# TouchGlove.net
KiCad netlist of a schematic drawn in EAGLE
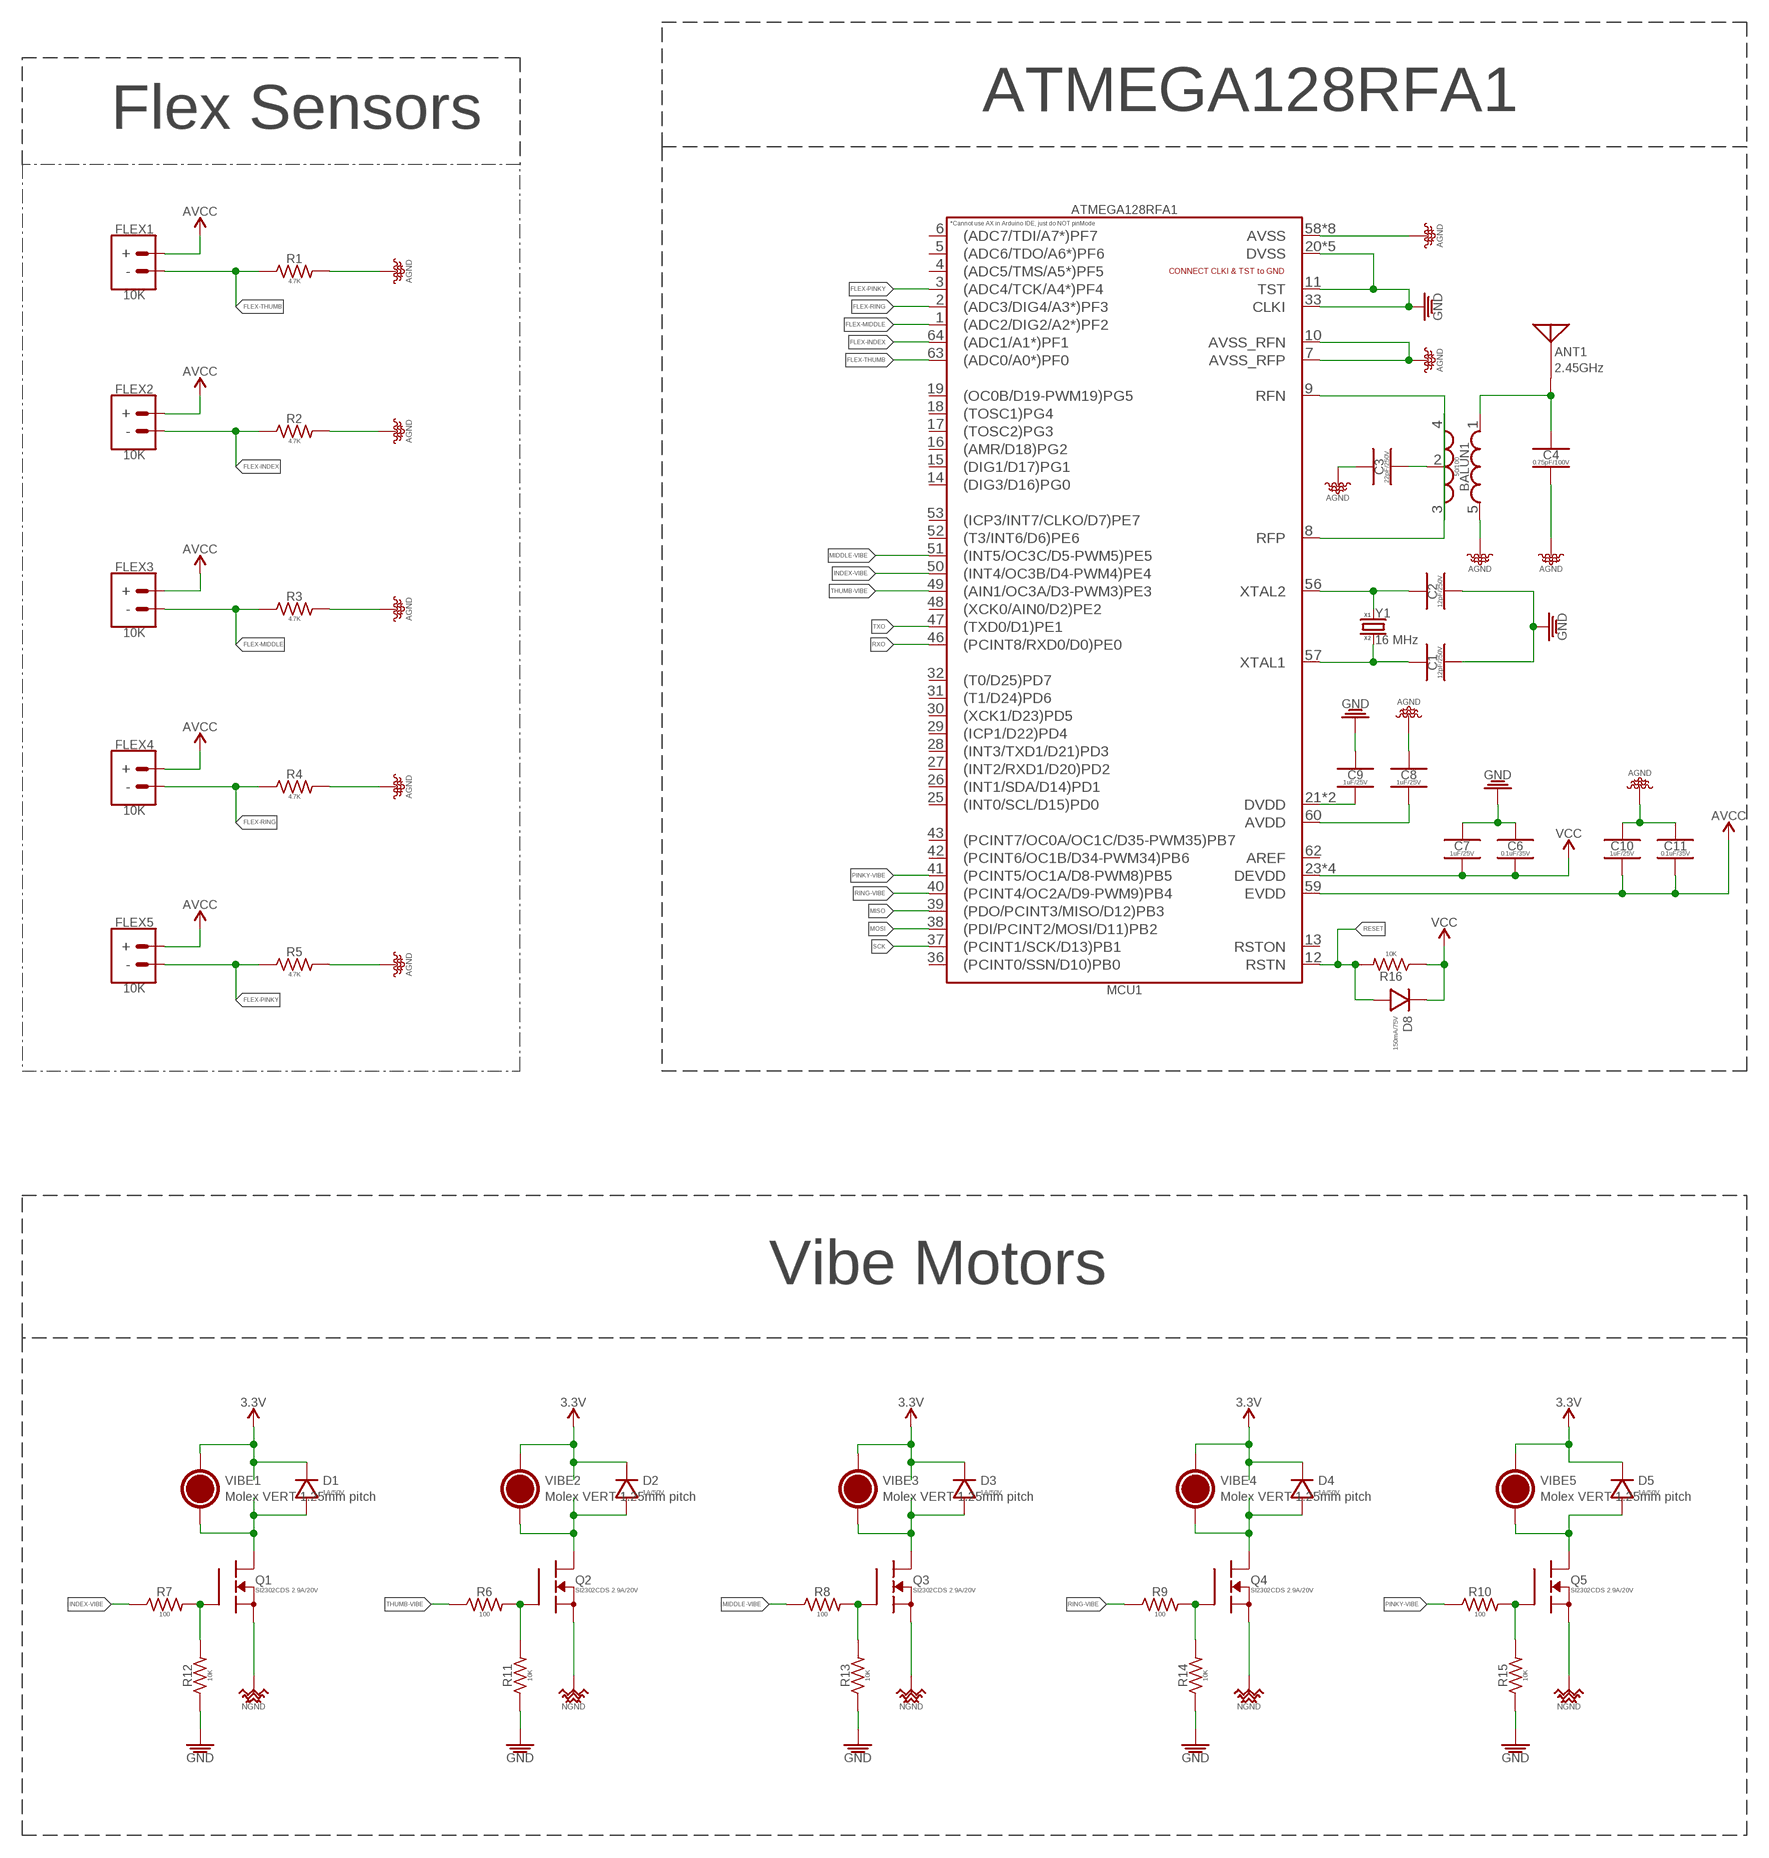
[diagram p0: schematic, sheet 1, part 1 of 2]
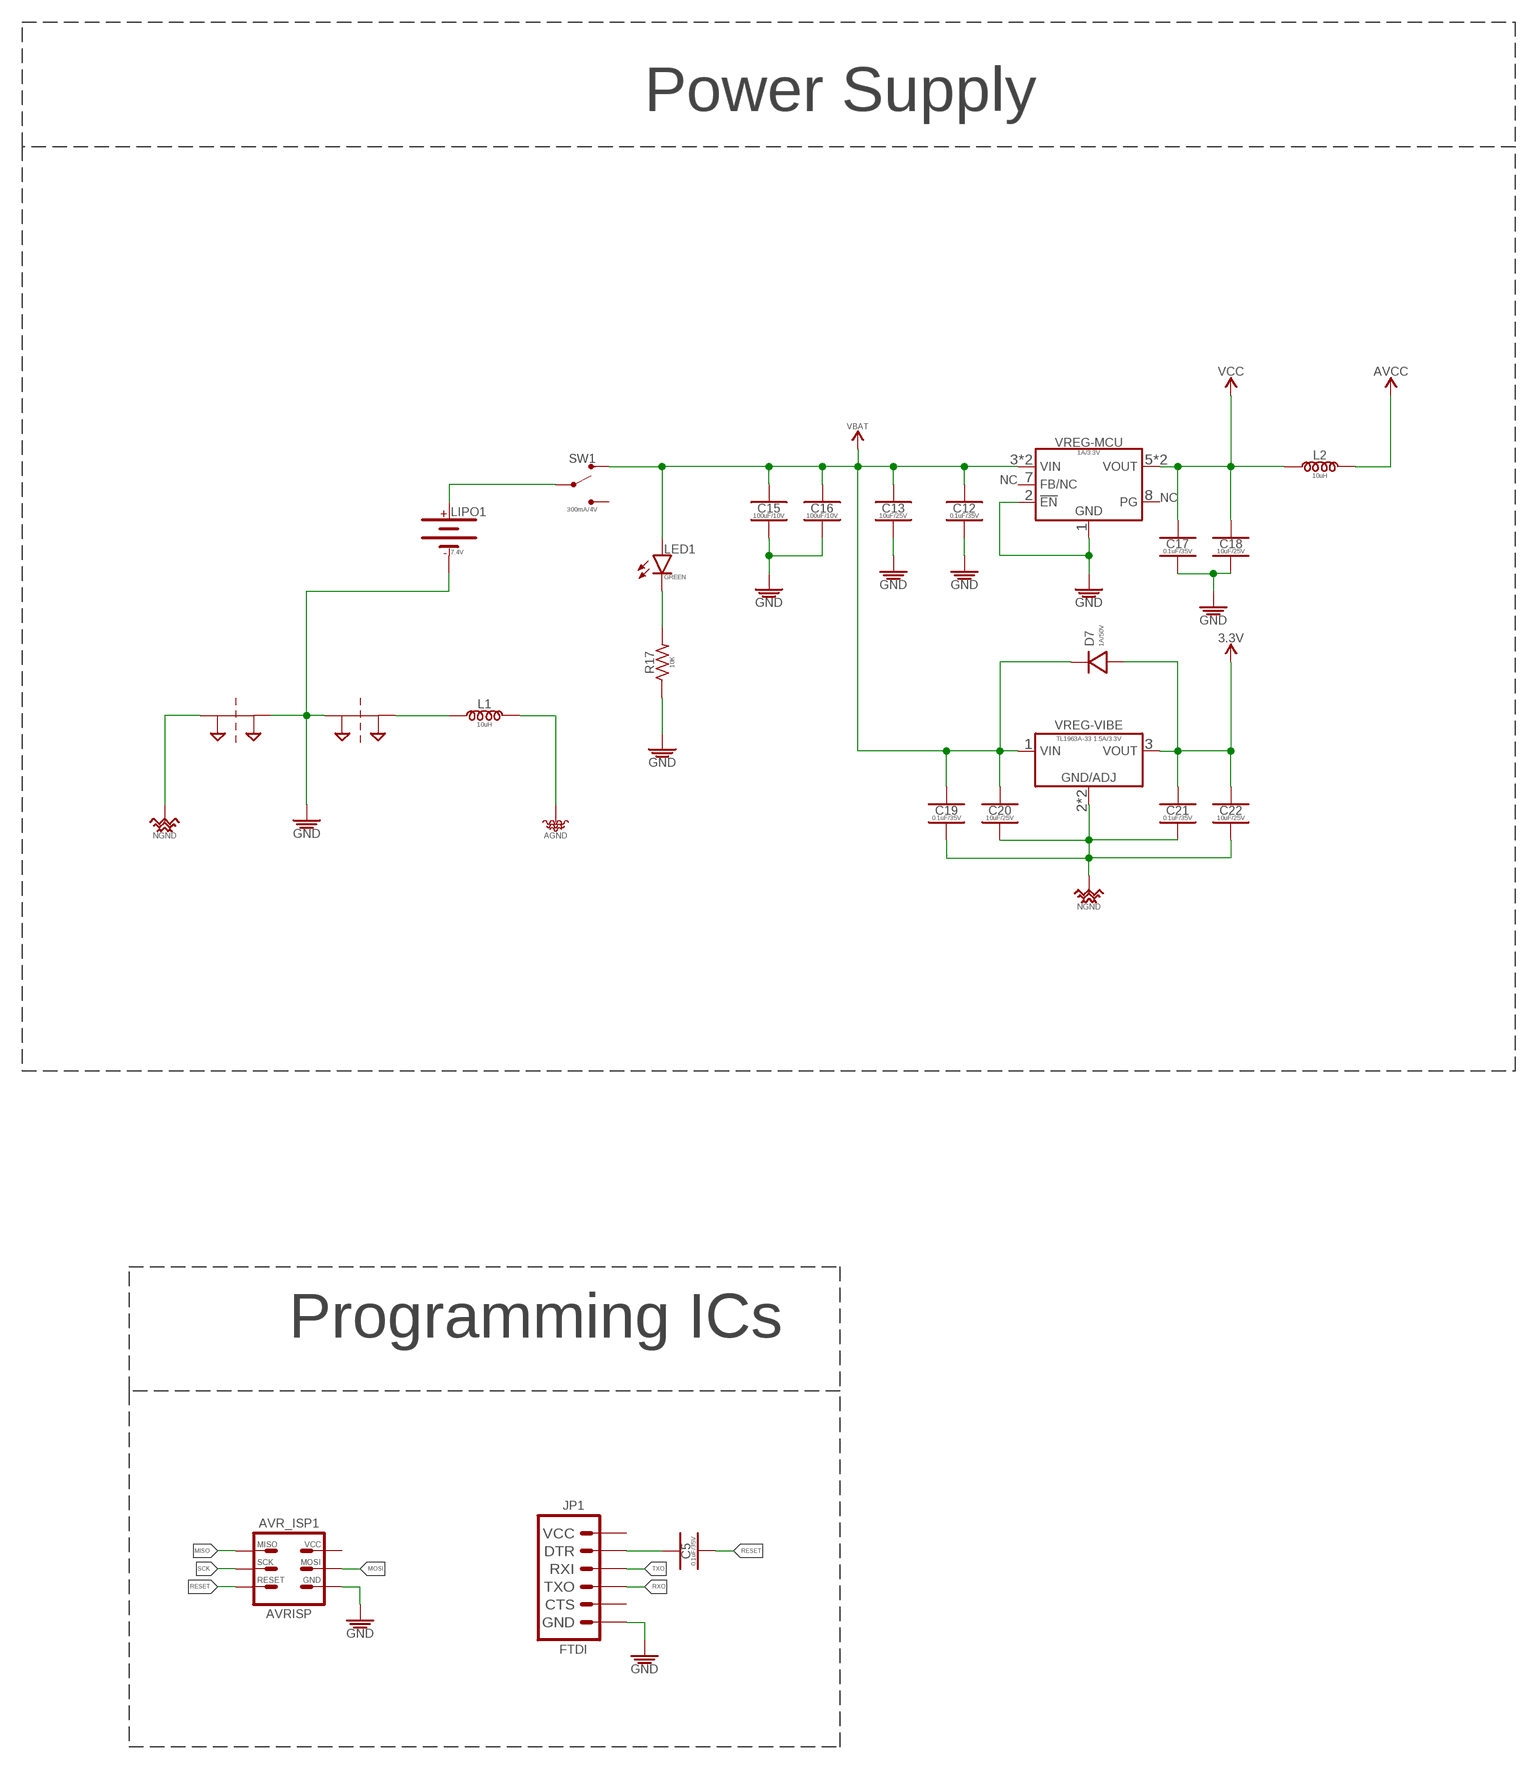
[diagram p1: schematic, sheet 1, part 2 of 2]

(export (version "E")
  (design (tool "Eeschema 10.0.6"))
  (components
    (comp (ref "ANT1")
      (value "2.45GHz")
      (footprint "eagle-import:ANTC6522X100")
      (fields (field (name "MFR") "Linx Technologies Inc.") (field (name "MPN") "ANT-2.45-CHP-T"))
      (libsource (lib "eagle-import") (part "ANTENNA_SMD_CHP-2.45GHZ-0.5DBI-3W"))
    )
    (comp (ref "AVR_ISP1")
      (value "AVRISP")
      (footprint "eagle-import:2X3-NS")
      (fields (field (name "MFR") "Amphenol FCI") (field (name "MPN") "67997-206HLF"))
      (libsource (lib "eagle-import") (part "AVR_SPI_PRG_6_PTH_VERT-MALE"))
    )
    (comp (ref "BALUN1")
      (value "50/100")
      (footprint "eagle-import:RESCAXE65P200X125X95-6")
      (fields (field (name "MFR") "Wurth Electronics Inc.") (field (name "MPN") "748421245"))
      (libsource (lib "eagle-import") (part "BALUN_SMD-0805_UNBAL/BAL-50/100"))
    )
    (comp (ref "C1")
      (value "12pF/250V")
      (footprint "eagle-import:CAPC2012X95_SMD-0805")
      (fields
        (field (name "MFR") "Murata Electronics North America")
        (field (name "MPN") "GRM21A5C2E120JW01D")
      )
      (libsource (lib "eagle-import") (part "12PF_SMD-0805_250V-5%"))
    )
    (comp (ref "C2")
      (value "12pF/250V")
      (footprint "eagle-import:CAPC2012X95_SMD-0805")
      (fields
        (field (name "MFR") "Murata Electronics North America")
        (field (name "MPN") "GRM21A5C2E120JW01D")
      )
      (libsource (lib "eagle-import") (part "12PF_SMD-0805_250V-5%"))
    )
    (comp (ref "C3")
      (value "22pF/250V")
      (footprint "eagle-import:CAPC2012X95_SMD-0805")
      (fields
        (field (name "MFR") "Murata Electronics North America")
        (field (name "MPN") "GRM21A5C2E220JW01D")
      )
      (libsource (lib "eagle-import") (part "22PF_CER_SMD-0805_250V-5%"))
    )
    (comp (ref "C4")
      (value "0.75pF/100V")
      (footprint "eagle-import:CAPC2012X95_SMD-0805")
      (fields
        (field (name "MFR") "Murata Electronics North America")
        (field (name "MPN") "GQM2195C2AR75CB01D")
      )
      (libsource (lib "eagle-import") (part "0.75PF_CER_SMD-0805_100V-33%"))
    )
    (comp (ref "C5")
      (value "0.1uF/35V")
      (footprint "eagle-import:CAPC2012X95_SMD-0805")
      (fields (field (name "MFR") "Taiyo Yuden") (field (name "MPN") "GMK212BJ104KGHT"))
      (libsource (lib "eagle-import") (part "0.1UF_SMD-0805_35V-10%"))
    )
    (comp (ref "C6")
      (value "0.1uF/35V")
      (footprint "eagle-import:CAPC2012X95_SMD-0805")
      (fields (field (name "MFR") "Taiyo Yuden") (field (name "MPN") "GMK212BJ104KGHT"))
      (libsource (lib "eagle-import") (part "0.1UF_SMD-0805_35V-10%"))
    )
    (comp (ref "C7")
      (value "1uF/25V")
      (footprint "eagle-import:CAPC2012X95_SMD-0805")
      (fields
        (field (name "MFR") "Murata Electronics North America")
        (field (name "MPN") "GRM216R61E105KA12D")
      )
      (libsource (lib "eagle-import") (part "1UF_CER_SMD-0805_25V-10%"))
    )
    (comp (ref "C8")
      (value "1uF/25V")
      (footprint "eagle-import:CAPC2012X95_SMD-0805")
      (fields
        (field (name "MFR") "Murata Electronics North America")
        (field (name "MPN") "GRM216R61E105KA12D")
      )
      (libsource (lib "eagle-import") (part "1UF_CER_SMD-0805_25V-10%"))
    )
    (comp (ref "C9")
      (value "1uF/25V")
      (footprint "eagle-import:CAPC2012X95_SMD-0805")
      (fields
        (field (name "MFR") "Murata Electronics North America")
        (field (name "MPN") "GRM216R61E105KA12D")
      )
      (libsource (lib "eagle-import") (part "1UF_CER_SMD-0805_25V-10%"))
    )
    (comp (ref "C10")
      (value "1uF/25V")
      (footprint "eagle-import:CAPC2012X95_SMD-0805")
      (fields
        (field (name "MFR") "Murata Electronics North America")
        (field (name "MPN") "GRM216R61E105KA12D")
      )
      (libsource (lib "eagle-import") (part "1UF_CER_SMD-0805_25V-10%"))
    )
    (comp (ref "C11")
      (value "0.1uF/35V")
      (footprint "eagle-import:CAPC2012X95_SMD-0805")
      (fields (field (name "MFR") "Taiyo Yuden") (field (name "MPN") "GMK212BJ104KGHT"))
      (libsource (lib "eagle-import") (part "0.1UF_SMD-0805_35V-10%"))
    )
    (comp (ref "C12")
      (value "0.1uF/35V")
      (footprint "eagle-import:CAPC2012X95_SMD-0805")
      (fields (field (name "MFR") "Taiyo Yuden") (field (name "MPN") "GMK212BJ104KGHT"))
      (libsource (lib "eagle-import") (part "0.1UF_SMD-0805_35V-10%"))
    )
    (comp (ref "C13")
      (value "10uF/25V")
      (footprint "eagle-import:CAPC2012X95_SMD-0805")
      (fields (field (name "MFR") "Taiyo Yuden") (field (name "MPN") "TMK212BBJ106KG-T"))
      (libsource (lib "eagle-import") (part "10UF_CER_SMD-0805_25V-10%"))
    )
    (comp (ref "C15")
      (value "100uF/10V")
      (footprint "eagle-import:CAPC3225X270_SMD-1210")
      (fields (field (name "MFR") "Taiyo Yuden") (field (name "MPN") "LMK325ABJ107MMHT"))
      (libsource (lib "eagle-import") (part "100UF_CER_SMD-1210_16V-20%"))
    )
    (comp (ref "C16")
      (value "100uF/10V")
      (footprint "eagle-import:CAPC3225X270_SMD-1210")
      (fields (field (name "MFR") "Taiyo Yuden") (field (name "MPN") "LMK325ABJ107MMHT"))
      (libsource (lib "eagle-import") (part "100UF_CER_SMD-1210_16V-20%"))
    )
    (comp (ref "C17")
      (value "0.1uF/35V")
      (footprint "eagle-import:CAPC2012X95_SMD-0805")
      (fields (field (name "MFR") "Taiyo Yuden") (field (name "MPN") "GMK212BJ104KGHT"))
      (libsource (lib "eagle-import") (part "0.1UF_SMD-0805_35V-10%"))
    )
    (comp (ref "C18")
      (value "10uF/25V")
      (footprint "eagle-import:CAPC2012X95_SMD-0805")
      (fields (field (name "MFR") "Taiyo Yuden") (field (name "MPN") "TMK212BBJ106KG-T"))
      (libsource (lib "eagle-import") (part "10UF_CER_SMD-0805_25V-10%"))
    )
    (comp (ref "C19")
      (value "0.1uF/35V")
      (footprint "eagle-import:CAPC2012X95_SMD-0805")
      (fields (field (name "MFR") "Taiyo Yuden") (field (name "MPN") "GMK212BJ104KGHT"))
      (libsource (lib "eagle-import") (part "0.1UF_SMD-0805_35V-10%"))
    )
    (comp (ref "C20")
      (value "10uF/25V")
      (footprint "eagle-import:CAPC2012X95_SMD-0805")
      (fields (field (name "MFR") "Taiyo Yuden") (field (name "MPN") "TMK212BBJ106KG-T"))
      (libsource (lib "eagle-import") (part "10UF_CER_SMD-0805_25V-10%"))
    )
    (comp (ref "C21")
      (value "0.1uF/35V")
      (footprint "eagle-import:CAPC2012X95_SMD-0805")
      (fields (field (name "MFR") "Taiyo Yuden") (field (name "MPN") "GMK212BJ104KGHT"))
      (libsource (lib "eagle-import") (part "0.1UF_SMD-0805_35V-10%"))
    )
    (comp (ref "C22")
      (value "10uF/25V")
      (footprint "eagle-import:CAPC2012X95_SMD-0805")
      (fields (field (name "MFR") "Taiyo Yuden") (field (name "MPN") "TMK212BBJ106KG-T"))
      (libsource (lib "eagle-import") (part "10UF_CER_SMD-0805_25V-10%"))
    )
    (comp (ref "D1")
      (value "1A/50V")
      (footprint "eagle-import:SODFL3516X170")
      (fields (field (name "MFR") "Comchip Technology") (field (name "MPN") "CGRKM4001-HF"))
      (libsource (lib "eagle-import") (part "DIODE_GENERAL-PURPOSE_SMD_GP_1A-50V"))
    )
    (comp (ref "D2")
      (value "1A/50V")
      (footprint "eagle-import:SODFL3516X170")
      (fields (field (name "MFR") "Comchip Technology") (field (name "MPN") "CGRKM4001-HF"))
      (libsource (lib "eagle-import") (part "DIODE_GENERAL-PURPOSE_SMD_GP_1A-50V"))
    )
    (comp (ref "D3")
      (value "1A/50V")
      (footprint "eagle-import:SODFL3516X170")
      (fields (field (name "MFR") "Comchip Technology") (field (name "MPN") "CGRKM4001-HF"))
      (libsource (lib "eagle-import") (part "DIODE_GENERAL-PURPOSE_SMD_GP_1A-50V"))
    )
    (comp (ref "D4")
      (value "1A/50V")
      (footprint "eagle-import:SODFL3516X170")
      (fields (field (name "MFR") "Comchip Technology") (field (name "MPN") "CGRKM4001-HF"))
      (libsource (lib "eagle-import") (part "DIODE_GENERAL-PURPOSE_SMD_GP_1A-50V"))
    )
    (comp (ref "D5")
      (value "1A/50V")
      (footprint "eagle-import:SODFL3516X170")
      (fields (field (name "MFR") "Comchip Technology") (field (name "MPN") "CGRKM4001-HF"))
      (libsource (lib "eagle-import") (part "DIODE_GENERAL-PURPOSE_SMD_GP_1A-50V"))
    )
    (comp (ref "D7")
      (value "1A/50V")
      (footprint "eagle-import:SODFL3516X170")
      (fields (field (name "MFR") "Comchip Technology") (field (name "MPN") "CGRKM4001-HF"))
      (libsource (lib "eagle-import") (part "DIODE_GENERAL-PURPOSE_SMD_GP_1A-50V"))
    )
    (comp (ref "D8")
      (value "150mA/75V")
      (footprint "eagle-import:DFN100X60X55-2")
      (fields (field (name "MFR") "Comchip Technology") (field (name "MPN") "CDSQR4148-HF"))
      (libsource (lib "eagle-import") (part "DIODE_GENERAL-PURPOSE_SMD-0402_GP_150MA-75V"))
    )
    (comp (ref "FLEX1")
      (value "10K")
      (footprint "eagle-import:_MOLEX-0530470210_VERT_PITCH-1.25MM")
      (fields (field (name "MFR") "Spectra Symbol") (field (name "MPN") "FS-L-0095-103-ST"))
      (libsource (lib "eagle-import") (part "FLEX_SENSOR_0530470210_VERT-MALE_PITCH-1.25MM"))
    )
    (comp (ref "FLEX2")
      (value "10K")
      (footprint "eagle-import:_MOLEX-0530470210_VERT_PITCH-1.25MM")
      (fields (field (name "MFR") "Spectra Symbol") (field (name "MPN") "FS-L-0095-103-ST"))
      (libsource (lib "eagle-import") (part "FLEX_SENSOR_0530470210_VERT-MALE_PITCH-1.25MM"))
    )
    (comp (ref "FLEX3")
      (value "10K")
      (footprint "eagle-import:_MOLEX-0530470210_VERT_PITCH-1.25MM")
      (fields (field (name "MFR") "Spectra Symbol") (field (name "MPN") "FS-L-0095-103-ST"))
      (libsource (lib "eagle-import") (part "FLEX_SENSOR_0530470210_VERT-MALE_PITCH-1.25MM"))
    )
    (comp (ref "FLEX4")
      (value "10K")
      (footprint "eagle-import:_MOLEX-0530470210_VERT_PITCH-1.25MM")
      (fields (field (name "MFR") "Spectra Symbol") (field (name "MPN") "FS-L-0095-103-ST"))
      (libsource (lib "eagle-import") (part "FLEX_SENSOR_0530470210_VERT-MALE_PITCH-1.25MM"))
    )
    (comp (ref "FLEX5")
      (value "10K")
      (footprint "eagle-import:_MOLEX-0530470210_VERT_PITCH-1.25MM")
      (fields (field (name "MFR") "Spectra Symbol") (field (name "MPN") "FS-L-0095-103-ST"))
      (libsource (lib "eagle-import") (part "FLEX_SENSOR_0530470210_VERT-MALE_PITCH-1.25MM"))
    )
    (comp (ref "JP1")
      (value "FTDI")
      (footprint "eagle-import:FTDI_BASIC-6PIN-MALE-RA")
      (fields (field (name "MFR") "SparkFun Electronics") (field (name "MPN") "DEV-09873"))
      (libsource (lib "eagle-import") (part "FTDI_PTH_RA-MALE"))
    )
    (comp (ref "L1")
      (value "10uH")
      (footprint "eagle-import:INDC2012X145")
      (fields (field (name "MFR") "Taiyo Yuden") (field (name "MPN") "CB2012T100KR"))
      (libsource (lib "eagle-import") (part "10UH_SMD-0805_0.5A-0.65OHM-10%"))
    )
    (comp (ref "L2")
      (value "10uH")
      (footprint "eagle-import:INDC2012X145")
      (fields (field (name "MFR") "Taiyo Yuden") (field (name "MPN") "CB2012T100KR"))
      (libsource (lib "eagle-import") (part "10UH_SMD-0805_0.5A-0.65OHM-10%"))
    )
    (comp (ref "LED1")
      (value "GREEN")
      (footprint "eagle-import:LEDC2012X120_LED-0805")
      (fields (field (name "MFR") "Lite-On Inc.") (field (name "MPN") "LTST-C170KGKT"))
      (libsource (lib "eagle-import") (part "LED_SMD-0805_DISCRETE_GREEN_"))
    )
    (comp (ref "LIPO1")
      (value "7.4V")
      (footprint "eagle-import:BATTERY_MOLEX-89401_RA_PITCH-2MM")
      (fields (field (name "MFR") "Molex, LLC") (field (name "MPN") "0894010210"))
      (libsource (lib "eagle-import") (part "BATTERY-CONNECTOR_MOLEX_89401_RA-MALE_PITCH-2MM"))
    )
    (comp (ref "MCU1")
      (value "ATMEGA128RFA1")
      (footprint "eagle-import:QFN50P900X900X90-64")
      (fields (field (name "MFR") "Microchip Technology") (field (name "MPN") "ATMEGA128RFA1-ZU"))
      (libsource (lib "eagle-import") (part "ATMEGA128RFA1_VFQFN-64_EXPOSED-PAD"))
    )
    (comp (ref "Q1")
      (value "SI2302CDS 2.9A/20V")
      (footprint "eagle-import:SOT95P287X112-3")
      (fields (field (name "MFR") "Vishay Siliconix") (field (name "MPN") "SI2302DDS-T1-GE3"))
      (libsource (lib "eagle-import") (part "MOSFET_N-CHANNEL_SI2302CDS_2.9A-20V-0.057OHM_"))
    )
    (comp (ref "Q2")
      (value "SI2302CDS 2.9A/20V")
      (footprint "eagle-import:SOT95P287X112-3")
      (fields (field (name "MFR") "Vishay Siliconix") (field (name "MPN") "SI2302DDS-T1-GE3"))
      (libsource (lib "eagle-import") (part "MOSFET_N-CHANNEL_SI2302CDS_2.9A-20V-0.057OHM_"))
    )
    (comp (ref "Q3")
      (value "SI2302CDS 2.9A/20V")
      (footprint "eagle-import:SOT95P287X112-3")
      (fields (field (name "MFR") "Vishay Siliconix") (field (name "MPN") "SI2302DDS-T1-GE3"))
      (libsource (lib "eagle-import") (part "MOSFET_N-CHANNEL_SI2302CDS_2.9A-20V-0.057OHM_"))
    )
    (comp (ref "Q4")
      (value "SI2302CDS 2.9A/20V")
      (footprint "eagle-import:SOT95P287X112-3")
      (fields (field (name "MFR") "Vishay Siliconix") (field (name "MPN") "SI2302DDS-T1-GE3"))
      (libsource (lib "eagle-import") (part "MOSFET_N-CHANNEL_SI2302CDS_2.9A-20V-0.057OHM_"))
    )
    (comp (ref "Q5")
      (value "SI2302CDS 2.9A/20V")
      (footprint "eagle-import:SOT95P287X112-3")
      (fields (field (name "MFR") "Vishay Siliconix") (field (name "MPN") "SI2302DDS-T1-GE3"))
      (libsource (lib "eagle-import") (part "MOSFET_N-CHANNEL_SI2302CDS_2.9A-20V-0.057OHM_"))
    )
    (comp (ref "R1")
      (value "4.7K")
      (footprint "eagle-import:RESC2012X60_SMD-0805")
      (fields (field (name "MFR") "Yageo") (field (name "MPN") "RC0805JR-074K7P"))
      (libsource (lib "eagle-import") (part "4.7KΩ_SMD-0805_1/8W_5%"))
    )
    (comp (ref "R2")
      (value "4.7K")
      (footprint "eagle-import:RESC2012X60_SMD-0805")
      (fields (field (name "MFR") "Yageo") (field (name "MPN") "RC0805JR-074K7P"))
      (libsource (lib "eagle-import") (part "4.7KΩ_SMD-0805_1/8W_5%"))
    )
    (comp (ref "R3")
      (value "4.7K")
      (footprint "eagle-import:RESC2012X60_SMD-0805")
      (fields (field (name "MFR") "Yageo") (field (name "MPN") "RC0805JR-074K7P"))
      (libsource (lib "eagle-import") (part "4.7KΩ_SMD-0805_1/8W_5%"))
    )
    (comp (ref "R4")
      (value "4.7K")
      (footprint "eagle-import:RESC2012X60_SMD-0805")
      (fields (field (name "MFR") "Yageo") (field (name "MPN") "RC0805JR-074K7P"))
      (libsource (lib "eagle-import") (part "4.7KΩ_SMD-0805_1/8W_5%"))
    )
    (comp (ref "R5")
      (value "4.7K")
      (footprint "eagle-import:RESC2012X60_SMD-0805")
      (fields (field (name "MFR") "Yageo") (field (name "MPN") "RC0805JR-074K7P"))
      (libsource (lib "eagle-import") (part "4.7KΩ_SMD-0805_1/8W_5%"))
    )
    (comp (ref "R6")
      (value "100")
      (footprint "eagle-import:RESC2012X60_SMD-0805")
      (fields (field (name "MFR") "Yageo") (field (name "MPN") "AC0805JR-07100RL"))
      (libsource (lib "eagle-import") (part "100Ω_SMD-0805_1/8W-5%"))
    )
    (comp (ref "R7")
      (value "100")
      (footprint "eagle-import:RESC2012X60_SMD-0805")
      (fields (field (name "MFR") "Yageo") (field (name "MPN") "AC0805JR-07100RL"))
      (libsource (lib "eagle-import") (part "100Ω_SMD-0805_1/8W-5%"))
    )
    (comp (ref "R8")
      (value "100")
      (footprint "eagle-import:RESC2012X60_SMD-0805")
      (fields (field (name "MFR") "Yageo") (field (name "MPN") "AC0805JR-07100RL"))
      (libsource (lib "eagle-import") (part "100Ω_SMD-0805_1/8W-5%"))
    )
    (comp (ref "R9")
      (value "100")
      (footprint "eagle-import:RESC2012X60_SMD-0805")
      (fields (field (name "MFR") "Yageo") (field (name "MPN") "AC0805JR-07100RL"))
      (libsource (lib "eagle-import") (part "100Ω_SMD-0805_1/8W-5%"))
    )
    (comp (ref "R10")
      (value "100")
      (footprint "eagle-import:RESC2012X60_SMD-0805")
      (fields (field (name "MFR") "Yageo") (field (name "MPN") "AC0805JR-07100RL"))
      (libsource (lib "eagle-import") (part "100Ω_SMD-0805_1/8W-5%"))
    )
    (comp (ref "R11")
      (value "10K")
      (footprint "eagle-import:RESC2012X60_SMD-0805")
      (fields (field (name "MFR") "Yageo") (field (name "MPN") "RC0805JR-0710KL"))
      (libsource (lib "eagle-import") (part "10KΩ_SMD-0805_1/8W-5%"))
    )
    (comp (ref "R12")
      (value "10K")
      (footprint "eagle-import:RESC2012X60_SMD-0805")
      (fields (field (name "MFR") "Yageo") (field (name "MPN") "RC0805JR-0710KL"))
      (libsource (lib "eagle-import") (part "10KΩ_SMD-0805_1/8W-5%"))
    )
    (comp (ref "R13")
      (value "10K")
      (footprint "eagle-import:RESC2012X60_SMD-0805")
      (fields (field (name "MFR") "Yageo") (field (name "MPN") "RC0805JR-0710KL"))
      (libsource (lib "eagle-import") (part "10KΩ_SMD-0805_1/8W-5%"))
    )
    (comp (ref "R14")
      (value "10K")
      (footprint "eagle-import:RESC2012X60_SMD-0805")
      (fields (field (name "MFR") "Yageo") (field (name "MPN") "RC0805JR-0710KL"))
      (libsource (lib "eagle-import") (part "10KΩ_SMD-0805_1/8W-5%"))
    )
    (comp (ref "R15")
      (value "10K")
      (footprint "eagle-import:RESC2012X60_SMD-0805")
      (fields (field (name "MFR") "Yageo") (field (name "MPN") "RC0805JR-0710KL"))
      (libsource (lib "eagle-import") (part "10KΩ_SMD-0805_1/8W-5%"))
    )
    (comp (ref "R16")
      (value "10K")
      (footprint "eagle-import:RESC2012X60_SMD-0805")
      (fields (field (name "MFR") "Yageo") (field (name "MPN") "RC0805JR-0710KL"))
      (libsource (lib "eagle-import") (part "10KΩ_SMD-0805_1/8W-5%"))
    )
    (comp (ref "R17")
      (value "10K")
      (footprint "eagle-import:RESC2012X60_SMD-0805")
      (fields (field (name "MFR") "Yageo") (field (name "MPN") "RC0805JR-0710KL"))
      (libsource (lib "eagle-import") (part "10KΩ_SMD-0805_1/8W-5%"))
    )
    (comp (ref "SUPPLY38")
      (value "2PT_GND_TIE")
      (footprint "eagle-import:2PT_GND_TIE")
      (libsource (lib "eagle-import") (part "2PT_GND_TIE"))
    )
    (comp (ref "SUPPLY39")
      (value "2PT_GND_TIE")
      (footprint "eagle-import:2PT_GND_TIE")
      (libsource (lib "eagle-import") (part "2PT_GND_TIE"))
    )
    (comp (ref "SW1")
      (value "300mA/4V")
      (footprint "eagle-import:SW_SLIDE_SPDT_RA_SMD_4V_300MA_6.7L-2.6W")
      (fields
        (field (name "MFR") "APEM Inc.")
        (field (name "MPN") "MA12RTR")
        (field (name "CREATOR") "MrSwirlyEyes")
      )
      (libsource (lib "eagle-import") (part "SWITCH_SPDT_RA_SMD_300MA-4V_6.7L-2.6W"))
    )
    (comp (ref "VIBE1")
      (value "Molex VERT 1.25mm pitch")
      (footprint "eagle-import:_MOLEX-0530470210_VERT_PITCH-1.25MM")
      (fields (field (name "MFR") "Jinlong Machinery & Electronics, Inc.") (field (name "MPN") "C0825B002F"))
      (libsource (lib "eagle-import") (part "VIBE-MOTOR_CONNECTOR_0530470210_VERT-MALE_PITCH-1.25MM"))
    )
    (comp (ref "VIBE2")
      (value "Molex VERT 1.25mm pitch")
      (footprint "eagle-import:_MOLEX-0530470210_VERT_PITCH-1.25MM")
      (fields (field (name "MFR") "Jinlong Machinery & Electronics, Inc.") (field (name "MPN") "C0825B002F"))
      (libsource (lib "eagle-import") (part "VIBE-MOTOR_CONNECTOR_0530470210_VERT-MALE_PITCH-1.25MM"))
    )
    (comp (ref "VIBE3")
      (value "Molex VERT 1.25mm pitch")
      (footprint "eagle-import:_MOLEX-0530470210_VERT_PITCH-1.25MM")
      (fields (field (name "MFR") "Jinlong Machinery & Electronics, Inc.") (field (name "MPN") "C0825B002F"))
      (libsource (lib "eagle-import") (part "VIBE-MOTOR_CONNECTOR_0530470210_VERT-MALE_PITCH-1.25MM"))
    )
    (comp (ref "VIBE4")
      (value "Molex VERT 1.25mm pitch")
      (footprint "eagle-import:_MOLEX-0530470210_VERT_PITCH-1.25MM")
      (fields (field (name "MFR") "Jinlong Machinery & Electronics, Inc.") (field (name "MPN") "C0825B002F"))
      (libsource (lib "eagle-import") (part "VIBE-MOTOR_CONNECTOR_0530470210_VERT-MALE_PITCH-1.25MM"))
    )
    (comp (ref "VIBE5")
      (value "Molex VERT 1.25mm pitch")
      (footprint "eagle-import:_MOLEX-0530470210_VERT_PITCH-1.25MM")
      (fields (field (name "MFR") "Jinlong Machinery & Electronics, Inc.") (field (name "MPN") "C0825B002F"))
      (libsource (lib "eagle-import") (part "VIBE-MOTOR_CONNECTOR_0530470210_VERT-MALE_PITCH-1.25MM"))
    )
    (comp (ref "VREG-MCU")
      (value "1A/3.3V")
      (footprint "eagle-import:SOIC127P600X265-8")
      (fields (field (name "MFR") "Texas Instruments") (field (name "MPN") "TPS76833QDR"))
      (libsource (lib "eagle-import") (part "VREG_TPS768XX_ULDO_FAST-TRANSIENT_TPS76833QDR_1A-3.3V"))
    )
    (comp (ref "VREG-VIBE")
      (value "TL1963A-33 1.5A/3.3V")
      (footprint "eagle-import:SOT229P700X180-4")
      (fields (field (name "MFR") "Texas Instruments") (field (name "MPN") "TL1963A-33DCYR"))
      (libsource (lib "eagle-import") (part "VREG_TL1963A-XX_1.5A_LN_LDO_FAST-TRANSIENT_SOT-223-4_TL1963A-33_1.5A-3.3V"))
    )
    (comp (ref "Y1")
      (value "16 MHz")
      (footprint "eagle-import:OSCCC500X320X110")
      (fields (field (name "MFR") "Abracon LLC") (field (name "MPN") "ABM3B-16.000MHZ-B2-T"))
      (libsource (lib "eagle-import") (part "CRYSTAL_ABM3B_16MHZ_18PF"))
    )
  )
  (nets
    (net (code "1") (name "3.3V") (class "Default")
      (node (ref "C21") (pin "1") (pinfunction "1_1") (pintype "passive"))
      (node (ref "C22") (pin "1") (pinfunction "1_1") (pintype "passive"))
      (node (ref "D1") (pin "K") (pinfunction "K_K") (pintype "passive"))
      (node (ref "D2") (pin "K") (pinfunction "K_K") (pintype "passive"))
      (node (ref "D3") (pin "K") (pinfunction "K_K") (pintype "passive"))
      (node (ref "D4") (pin "K") (pinfunction "K_K") (pintype "passive"))
      (node (ref "D5") (pin "K") (pinfunction "K_K") (pintype "passive"))
      (node (ref "D7") (pin "A") (pinfunction "A_A") (pintype "passive"))
      (node (ref "VIBE1") (pin "1") (pinfunction "+_1") (pintype "passive"))
      (node (ref "VIBE2") (pin "1") (pinfunction "+_1") (pintype "passive"))
      (node (ref "VIBE3") (pin "1") (pinfunction "+_1") (pintype "passive"))
      (node (ref "VIBE4") (pin "1") (pinfunction "+_1") (pintype "passive"))
      (node (ref "VIBE5") (pin "1") (pinfunction "+_1") (pintype "passive"))
      (node (ref "VREG-VIBE") (pin "3") (pinfunction "VO_3") (pintype "power_in"))
    )
    (net (code "2") (name "AGND") (class "Default")
      (node (ref "BALUN1") (pin "5") (pinfunction "GND_5") (pintype "passive"))
      (node (ref "C10") (pin "1") (pinfunction "1_1") (pintype "passive"))
      (node (ref "C11") (pin "1") (pinfunction "1_1") (pintype "passive"))
      (node (ref "C3") (pin "1") (pinfunction "1_1") (pintype "passive"))
      (node (ref "C4") (pin "2") (pinfunction "2_2") (pintype "passive"))
      (node (ref "C8") (pin "1") (pinfunction "1_1") (pintype "passive"))
      (node (ref "L1") (pin "2") (pinfunction "2_2") (pintype "passive"))
      (node (ref "MCU1") (pin "10") (pinfunction "AVSS_RFN_10") (pintype "power_in"))
      (node (ref "MCU1") (pin "58") (pinfunction "AVSS_58") (pintype "power_in"))
      (node (ref "MCU1") (pin "61") (pinfunction "AVSS_61") (pintype "power_in"))
      (node (ref "MCU1") (pin "7") (pinfunction "AVSS_RFP_7") (pintype "power_in"))
      (node (ref "MCU1") (pin "EP") (pinfunction "AVSS_EP") (pintype "power_in"))
      (node (ref "MCU1") (pin "P$1") (pinfunction "AVSS_P$1") (pintype "power_in"))
      (node (ref "MCU1") (pin "P$2") (pinfunction "AVSS_P$2") (pintype "power_in"))
      (node (ref "MCU1") (pin "P$3") (pinfunction "AVSS_P$3") (pintype "power_in"))
      (node (ref "MCU1") (pin "P$4") (pinfunction "AVSS_P$4") (pintype "power_in"))
      (node (ref "MCU1") (pin "P$5") (pinfunction "AVSS_P$5") (pintype "power_in"))
      (node (ref "R1") (pin "2") (pinfunction "2_2") (pintype "passive"))
      (node (ref "R2") (pin "2") (pinfunction "2_2") (pintype "passive"))
      (node (ref "R3") (pin "2") (pinfunction "2_2") (pintype "passive"))
      (node (ref "R4") (pin "2") (pinfunction "2_2") (pintype "passive"))
      (node (ref "R5") (pin "2") (pinfunction "2_2") (pintype "passive"))
    )
    (net (code "3") (name "AVCC") (class "Default")
      (node (ref "C10") (pin "2") (pinfunction "2_2") (pintype "passive"))
      (node (ref "C11") (pin "2") (pinfunction "2_2") (pintype "passive"))
      (node (ref "FLEX1") (pin "1") (pinfunction "+_1") (pintype "passive"))
      (node (ref "FLEX2") (pin "1") (pinfunction "+_1") (pintype "passive"))
      (node (ref "FLEX3") (pin "1") (pinfunction "+_1") (pintype "passive"))
      (node (ref "FLEX4") (pin "1") (pinfunction "+_1") (pintype "passive"))
      (node (ref "FLEX5") (pin "1") (pinfunction "+_1") (pintype "passive"))
      (node (ref "L2") (pin "2") (pinfunction "2_2") (pintype "passive"))
      (node (ref "MCU1") (pin "59") (pinfunction "EVDD_59") (pintype "power_in"))
    )
    (net (code "4") (name "FLEX-INDEX") (class "Default")
      (node (ref "FLEX2") (pin "2") (pinfunction "-_2") (pintype "passive"))
      (node (ref "MCU1") (pin "64") (pinfunction "(ADC1/A1*)PF1_64") (pintype "bidirectional"))
      (node (ref "R2") (pin "1") (pinfunction "1_1") (pintype "passive"))
    )
    (net (code "5") (name "FLEX-MIDDLE") (class "Default")
      (node (ref "FLEX3") (pin "2") (pinfunction "-_2") (pintype "passive"))
      (node (ref "MCU1") (pin "1") (pinfunction "(ADC2/DIG2/A2*)PF2_1") (pintype "bidirectional"))
      (node (ref "R3") (pin "1") (pinfunction "1_1") (pintype "passive"))
    )
    (net (code "6") (name "FLEX-PINKY") (class "Default")
      (node (ref "FLEX5") (pin "2") (pinfunction "-_2") (pintype "passive"))
      (node (ref "MCU1") (pin "3") (pinfunction "(ADC4/TCK/A4*)PF4_3") (pintype "bidirectional"))
      (node (ref "R5") (pin "1") (pinfunction "1_1") (pintype "passive"))
    )
    (net (code "7") (name "FLEX-RING") (class "Default")
      (node (ref "FLEX4") (pin "2") (pinfunction "-_2") (pintype "passive"))
      (node (ref "MCU1") (pin "2") (pinfunction "(ADC3/DIG4/A3*)PF3_2") (pintype "bidirectional"))
      (node (ref "R4") (pin "1") (pinfunction "1_1") (pintype "passive"))
    )
    (net (code "8") (name "FLEX-THUMB") (class "Default")
      (node (ref "FLEX1") (pin "2") (pinfunction "-_2") (pintype "passive"))
      (node (ref "MCU1") (pin "63") (pinfunction "(ADC0/A0*)PF0_63") (pintype "bidirectional"))
      (node (ref "R1") (pin "1") (pinfunction "1_1") (pintype "passive"))
    )
    (net (code "9") (name "GND") (class "Default")
      (node (ref "AVR_ISP1") (pin "GND") (pinfunction "GND_GND") (pintype "power_in"))
      (node (ref "C1") (pin "2") (pinfunction "2_2") (pintype "passive"))
      (node (ref "C12") (pin "2") (pinfunction "2_2") (pintype "passive"))
      (node (ref "C13") (pin "2") (pinfunction "2_2") (pintype "passive"))
      (node (ref "C15") (pin "2") (pinfunction "2_2") (pintype "passive"))
      (node (ref "C16") (pin "2") (pinfunction "2_2") (pintype "passive"))
      (node (ref "C17") (pin "2") (pinfunction "2_2") (pintype "passive"))
      (node (ref "C18") (pin "2") (pinfunction "2_2") (pintype "passive"))
      (node (ref "C2") (pin "2") (pinfunction "2_2") (pintype "passive"))
      (node (ref "C6") (pin "1") (pinfunction "1_1") (pintype "passive"))
      (node (ref "C7") (pin "1") (pinfunction "1_1") (pintype "passive"))
      (node (ref "C9") (pin "1") (pinfunction "1_1") (pintype "passive"))
      (node (ref "JP1") (pin "GND") (pinfunction "GND_GND") (pintype "power_in"))
      (node (ref "LIPO1") (pin "-") (pinfunction "-_-") (pintype "power_in"))
      (node (ref "MCU1") (pin "11") (pinfunction "TST_11") (pintype "power_in"))
      (node (ref "MCU1") (pin "20") (pinfunction "DVSS_20") (pintype "power_in"))
      (node (ref "MCU1") (pin "24") (pinfunction "DVSS_24") (pintype "power_in"))
      (node (ref "MCU1") (pin "33") (pinfunction "CLKI_33") (pintype "power_in"))
      (node (ref "MCU1") (pin "35") (pinfunction "DVSS_35") (pintype "power_in"))
      (node (ref "MCU1") (pin "45") (pinfunction "DVSS_45") (pintype "power_in"))
      (node (ref "MCU1") (pin "55") (pinfunction "DVSS_55") (pintype "power_in"))
      (node (ref "R11") (pin "1") (pinfunction "1_1") (pintype "passive"))
      (node (ref "R12") (pin "1") (pinfunction "1_1") (pintype "passive"))
      (node (ref "R13") (pin "1") (pinfunction "1_1") (pintype "passive"))
      (node (ref "R14") (pin "1") (pinfunction "1_1") (pintype "passive"))
      (node (ref "R15") (pin "1") (pinfunction "1_1") (pintype "passive"))
      (node (ref "R17") (pin "1") (pinfunction "1_1") (pintype "passive"))
      (node (ref "SUPPLY38") (pin "P$2") (pinfunction "P$2_P$2") (pintype "passive"))
      (node (ref "SUPPLY39") (pin "P$1") (pinfunction "P$1_P$1") (pintype "passive"))
      (node (ref "VREG-MCU") (pin "1") (pinfunction "GND_1") (pintype "power_in"))
      (node (ref "VREG-MCU") (pin "2") (pinfunction "~{EN}_2") (pintype "power_in"))
    )
    (net (code "10") (name "INDEX-VIBE") (class "Default")
      (node (ref "MCU1") (pin "50") (pinfunction "(INT4/OC3B/D4-PWM4)PE4_50") (pintype "bidirectional"))
      (node (ref "R7") (pin "1") (pinfunction "1_1") (pintype "passive"))
    )
    (net (code "11") (name "MIDDLE-VIBE") (class "Default")
      (node (ref "MCU1") (pin "51") (pinfunction "(INT5/OC3C/D5-PWM5)PE5_51") (pintype "bidirectional"))
      (node (ref "R8") (pin "1") (pinfunction "1_1") (pintype "passive"))
    )
    (net (code "12") (name "MISO") (class "Default")
      (node (ref "AVR_ISP1") (pin "MISO") (pinfunction "MISO_MISO") (pintype "bidirectional"))
      (node (ref "MCU1") (pin "39") (pinfunction "(PDO/PCINT3/MISO/D12)PB3_39") (pintype "bidirectional"))
    )
    (net (code "13") (name "MOSI") (class "Default")
      (node (ref "AVR_ISP1") (pin "MOSI") (pinfunction "MOSI_MOSI") (pintype "bidirectional"))
      (node (ref "MCU1") (pin "38") (pinfunction "(PDI/PCINT2/MOSI/D11)PB2_38") (pintype "bidirectional"))
    )
    (net (code "14") (name "NGND") (class "Default")
      (node (ref "C19") (pin "2") (pinfunction "2_2") (pintype "passive"))
      (node (ref "C20") (pin "2") (pinfunction "2_2") (pintype "passive"))
      (node (ref "C21") (pin "2") (pinfunction "2_2") (pintype "passive"))
      (node (ref "C22") (pin "2") (pinfunction "2_2") (pintype "passive"))
      (node (ref "Q1") (pin "2") (pinfunction "S_2") (pintype "passive"))
      (node (ref "Q2") (pin "2") (pinfunction "S_2") (pintype "passive"))
      (node (ref "Q3") (pin "2") (pinfunction "S_2") (pintype "passive"))
      (node (ref "Q4") (pin "2") (pinfunction "S_2") (pintype "passive"))
      (node (ref "Q5") (pin "2") (pinfunction "S_2") (pintype "passive"))
      (node (ref "SUPPLY38") (pin "P$1") (pinfunction "P$1_P$1") (pintype "passive"))
      (node (ref "VREG-VIBE") (pin "2") (pinfunction "GND_2") (pintype "power_in"))
      (node (ref "VREG-VIBE") (pin "4") (pinfunction "GND_4") (pintype "power_in"))
    )
    (net (code "15") (name "Net-(ANT1-SIGNAL)") (class "Default")
      (node (ref "ANT1") (pin "1") (pinfunction "SIGNAL_1") (pintype "passive"))
      (node (ref "BALUN1") (pin "1") (pinfunction "IN_1") (pintype "passive"))
      (node (ref "C4") (pin "1") (pinfunction "1_1") (pintype "passive"))
    )
    (net (code "16") (name "Net-(BALUN1-GND-Pad2)") (class "Default")
      (node (ref "BALUN1") (pin "2") (pinfunction "GND_2") (pintype "passive"))
      (node (ref "C3") (pin "2") (pinfunction "2_2") (pintype "passive"))
    )
    (net (code "17") (name "Net-(BALUN1-OUT1)") (class "Default")
      (node (ref "BALUN1") (pin "3") (pinfunction "OUT1_3") (pintype "passive"))
      (node (ref "MCU1") (pin "9") (pinfunction "RFN_9") (pintype "passive"))
    )
    (net (code "18") (name "Net-(BALUN1-OUT2)") (class "Default")
      (node (ref "BALUN1") (pin "4") (pinfunction "OUT2_4") (pintype "passive"))
      (node (ref "MCU1") (pin "8") (pinfunction "RFP_8") (pintype "passive"))
    )
    (net (code "19") (name "Net-(C5-Pad1)") (class "Default")
      (node (ref "C5") (pin "1") (pinfunction "1_1") (pintype "passive"))
      (node (ref "JP1") (pin "DTR") (pinfunction "DTR_DTR") (pintype "bidirectional"))
    )
    (net (code "20") (name "Net-(C9-Pad2)") (class "Default")
      (node (ref "C9") (pin "2") (pinfunction "2_2") (pintype "passive"))
      (node (ref "MCU1") (pin "21") (pinfunction "DVDD_21") (pintype "passive"))
      (node (ref "MCU1") (pin "22") (pinfunction "DVDD_22") (pintype "passive"))
    )
    (net (code "21") (name "Net-(L1-Pad1)") (class "Default")
      (node (ref "L1") (pin "1") (pinfunction "1_1") (pintype "passive"))
      (node (ref "SUPPLY39") (pin "P$2") (pinfunction "P$2_P$2") (pintype "passive"))
    )
    (net (code "22") (name "Net-(LED1-PadK)") (class "Default")
      (node (ref "LED1") (pin "K") (pinfunction "K_K") (pintype "passive"))
      (node (ref "R17") (pin "2") (pinfunction "2_2") (pintype "passive"))
    )
    (net (code "23") (name "Net-(MCU1-AVDD)") (class "Default")
      (node (ref "C8") (pin "2") (pinfunction "2_2") (pintype "passive"))
      (node (ref "MCU1") (pin "60") (pinfunction "AVDD_60") (pintype "passive"))
    )
    (net (code "24") (name "Net-(MCU1-XTAL1)") (class "Default")
      (node (ref "C1") (pin "1") (pinfunction "1_1") (pintype "passive"))
      (node (ref "MCU1") (pin "57") (pinfunction "XTAL1_57") (pintype "passive"))
      (node (ref "Y1") (pin "3") (pinfunction "XTAL2_3") (pintype "passive"))
    )
    (net (code "25") (name "Net-(MCU1-XTAL2)") (class "Default")
      (node (ref "C2") (pin "1") (pinfunction "1_1") (pintype "passive"))
      (node (ref "MCU1") (pin "56") (pinfunction "XTAL2_56") (pintype "passive"))
      (node (ref "Y1") (pin "1") (pinfunction "XTAL1_1") (pintype "passive"))
    )
    (net (code "26") (name "Net-(Q1-D)") (class "Default")
      (node (ref "D1") (pin "A") (pinfunction "A_A") (pintype "passive"))
      (node (ref "Q1") (pin "3") (pinfunction "D_3") (pintype "passive"))
      (node (ref "VIBE1") (pin "2") (pinfunction "-_2") (pintype "passive"))
    )
    (net (code "27") (name "Net-(Q1-G)") (class "Default")
      (node (ref "Q1") (pin "1") (pinfunction "G_1") (pintype "passive"))
      (node (ref "R12") (pin "2") (pinfunction "2_2") (pintype "passive"))
      (node (ref "R7") (pin "2") (pinfunction "2_2") (pintype "passive"))
    )
    (net (code "28") (name "Net-(Q2-D)") (class "Default")
      (node (ref "D2") (pin "A") (pinfunction "A_A") (pintype "passive"))
      (node (ref "Q2") (pin "3") (pinfunction "D_3") (pintype "passive"))
      (node (ref "VIBE2") (pin "2") (pinfunction "-_2") (pintype "passive"))
    )
    (net (code "29") (name "Net-(Q2-G)") (class "Default")
      (node (ref "Q2") (pin "1") (pinfunction "G_1") (pintype "passive"))
      (node (ref "R11") (pin "2") (pinfunction "2_2") (pintype "passive"))
      (node (ref "R6") (pin "2") (pinfunction "2_2") (pintype "passive"))
    )
    (net (code "30") (name "Net-(Q3-D)") (class "Default")
      (node (ref "D3") (pin "A") (pinfunction "A_A") (pintype "passive"))
      (node (ref "Q3") (pin "3") (pinfunction "D_3") (pintype "passive"))
      (node (ref "VIBE3") (pin "2") (pinfunction "-_2") (pintype "passive"))
    )
    (net (code "31") (name "Net-(Q3-G)") (class "Default")
      (node (ref "Q3") (pin "1") (pinfunction "G_1") (pintype "passive"))
      (node (ref "R13") (pin "2") (pinfunction "2_2") (pintype "passive"))
      (node (ref "R8") (pin "2") (pinfunction "2_2") (pintype "passive"))
    )
    (net (code "32") (name "Net-(Q4-D)") (class "Default")
      (node (ref "D4") (pin "A") (pinfunction "A_A") (pintype "passive"))
      (node (ref "Q4") (pin "3") (pinfunction "D_3") (pintype "passive"))
      (node (ref "VIBE4") (pin "2") (pinfunction "-_2") (pintype "passive"))
    )
    (net (code "33") (name "Net-(Q4-G)") (class "Default")
      (node (ref "Q4") (pin "1") (pinfunction "G_1") (pintype "passive"))
      (node (ref "R14") (pin "2") (pinfunction "2_2") (pintype "passive"))
      (node (ref "R9") (pin "2") (pinfunction "2_2") (pintype "passive"))
    )
    (net (code "34") (name "Net-(Q5-D)") (class "Default")
      (node (ref "D5") (pin "A") (pinfunction "A_A") (pintype "passive"))
      (node (ref "Q5") (pin "3") (pinfunction "D_3") (pintype "passive"))
      (node (ref "VIBE5") (pin "2") (pinfunction "-_2") (pintype "passive"))
    )
    (net (code "35") (name "Net-(Q5-G)") (class "Default")
      (node (ref "Q5") (pin "1") (pinfunction "G_1") (pintype "passive"))
      (node (ref "R10") (pin "2") (pinfunction "2_2") (pintype "passive"))
      (node (ref "R15") (pin "2") (pinfunction "2_2") (pintype "passive"))
    )
    (net (code "36") (name "Net-(SW1-P)") (class "Default")
      (node (ref "LIPO1") (pin "+") (pinfunction "+_+") (pintype "power_in"))
      (node (ref "SW1") (pin "2") (pinfunction "P_2") (pintype "passive"))
    )
    (net (code "37") (name "PINKY-VIBE") (class "Default")
      (node (ref "MCU1") (pin "41") (pinfunction "(PCINT5/OC1A/D8-PWM8)PB5_41") (pintype "bidirectional"))
      (node (ref "R10") (pin "1") (pinfunction "1_1") (pintype "passive"))
    )
    (net (code "38") (name "RESET") (class "Default")
      (node (ref "AVR_ISP1") (pin "RESET") (pinfunction "RESET_RESET") (pintype "bidirectional"))
      (node (ref "C5") (pin "2") (pinfunction "2_2") (pintype "passive"))
      (node (ref "D8") (pin "A") (pinfunction "A_A") (pintype "passive"))
      (node (ref "MCU1") (pin "12") (pinfunction "RSTN_12") (pintype "bidirectional"))
      (node (ref "R16") (pin "2") (pinfunction "2_2") (pintype "passive"))
    )
    (net (code "39") (name "RING-VIBE") (class "Default")
      (node (ref "MCU1") (pin "40") (pinfunction "(PCINT4/OC2A/D9-PWM9)PB4_40") (pintype "bidirectional"))
      (node (ref "R9") (pin "1") (pinfunction "1_1") (pintype "passive"))
    )
    (net (code "40") (name "RXO") (class "Default")
      (node (ref "JP1") (pin "TXO") (pinfunction "TXO_TXO") (pintype "output"))
      (node (ref "MCU1") (pin "46") (pinfunction "(PCINT8/RXD0/D0)PE0_46") (pintype "bidirectional"))
    )
    (net (code "41") (name "SCK") (class "Default")
      (node (ref "AVR_ISP1") (pin "SCK") (pinfunction "SCK_SCK") (pintype "bidirectional"))
      (node (ref "MCU1") (pin "37") (pinfunction "(PCINT1/SCK/D13)PB1_37") (pintype "bidirectional"))
    )
    (net (code "42") (name "THUMB-VIBE") (class "Default")
      (node (ref "MCU1") (pin "49") (pinfunction "(AIN1/OC3A/D3-PWM3)PE3_49") (pintype "bidirectional"))
      (node (ref "R6") (pin "1") (pinfunction "1_1") (pintype "passive"))
    )
    (net (code "43") (name "TXO") (class "Default")
      (node (ref "JP1") (pin "RXI") (pinfunction "RXI_RXI") (pintype "input"))
      (node (ref "MCU1") (pin "47") (pinfunction "(TXD0/D1)PE1_47") (pintype "bidirectional"))
    )
    (net (code "44") (name "VBAT") (class "Default")
      (node (ref "C12") (pin "1") (pinfunction "1_1") (pintype "passive"))
      (node (ref "C13") (pin "1") (pinfunction "1_1") (pintype "passive"))
      (node (ref "C15") (pin "1") (pinfunction "1_1") (pintype "passive"))
      (node (ref "C16") (pin "1") (pinfunction "1_1") (pintype "passive"))
      (node (ref "C19") (pin "1") (pinfunction "1_1") (pintype "passive"))
      (node (ref "C20") (pin "1") (pinfunction "1_1") (pintype "passive"))
      (node (ref "D7") (pin "K") (pinfunction "K_K") (pintype "passive"))
      (node (ref "LED1") (pin "A") (pinfunction "A_A") (pintype "passive"))
      (node (ref "SW1") (pin "1") (pinfunction "S1_1") (pintype "passive"))
      (node (ref "VREG-MCU") (pin "3") (pinfunction "VIN_3") (pintype "power_in"))
      (node (ref "VREG-MCU") (pin "4") (pinfunction "VIN_4") (pintype "power_in"))
      (node (ref "VREG-VIBE") (pin "1") (pinfunction "VI_1") (pintype "power_in"))
    )
    (net (code "45") (name "VCC") (class "Default")
      (node (ref "C17") (pin "1") (pinfunction "1_1") (pintype "passive"))
      (node (ref "C18") (pin "1") (pinfunction "1_1") (pintype "passive"))
      (node (ref "C6") (pin "2") (pinfunction "2_2") (pintype "passive"))
      (node (ref "C7") (pin "2") (pinfunction "2_2") (pintype "passive"))
      (node (ref "D8") (pin "K") (pinfunction "K_K") (pintype "passive"))
      (node (ref "L2") (pin "1") (pinfunction "1_1") (pintype "passive"))
      (node (ref "MCU1") (pin "23") (pinfunction "DEVDD_23") (pintype "power_in"))
      (node (ref "MCU1") (pin "34") (pinfunction "DEVDD_34") (pintype "power_in"))
      (node (ref "MCU1") (pin "44") (pinfunction "DEVDD_44") (pintype "power_in"))
      (node (ref "MCU1") (pin "54") (pinfunction "DEVDD_54") (pintype "power_in"))
      (node (ref "R16") (pin "1") (pinfunction "1_1") (pintype "passive"))
      (node (ref "VREG-MCU") (pin "5") (pinfunction "VOUT_5") (pintype "power_in"))
      (node (ref "VREG-MCU") (pin "6") (pinfunction "VOUT_6") (pintype "power_in"))
    )
    (net (code "46") (name "unconnected-(AVR_ISP1-PadVCC)") (class "Default")
      (node (ref "AVR_ISP1") (pin "VCC") (pinfunction "VCC_VCC") (pintype "no_connect"))
    )
    (net (code "47") (name "unconnected-(JP1-PadCTS)") (class "Default")
      (node (ref "JP1") (pin "CTS") (pinfunction "CTS_CTS") (pintype "bidirectional"))
    )
    (net (code "48") (name "unconnected-(JP1-PadVCC)") (class "Default")
      (node (ref "JP1") (pin "VCC") (pinfunction "VCC_VCC") (pintype "no_connect"))
    )
    (net (code "49") (name "unconnected-(MCU1-(ADC5{slash}TMS{slash}A5*)PF5-Pad4)") (class "Default")
      (node (ref "MCU1") (pin "4") (pinfunction "(ADC5/TMS/A5*)PF5_4") (pintype "bidirectional"))
    )
    (net (code "50") (name "unconnected-(MCU1-(ADC6{slash}TDO{slash}A6*)PF6-Pad5)") (class "Default")
      (node (ref "MCU1") (pin "5") (pinfunction "(ADC6/TDO/A6*)PF6_5") (pintype "bidirectional"))
    )
    (net (code "51") (name "unconnected-(MCU1-(ADC7{slash}TDI{slash}A7*)PF7-Pad6)") (class "Default")
      (node (ref "MCU1") (pin "6") (pinfunction "(ADC7/TDI/A7*)PF7_6") (pintype "bidirectional"))
    )
    (net (code "52") (name "unconnected-(MCU1-(AMR{slash}D18)PG2-Pad16)") (class "Default")
      (node (ref "MCU1") (pin "16") (pinfunction "(AMR/D18)PG2_16") (pintype "bidirectional"))
    )
    (net (code "53") (name "unconnected-(MCU1-(DIG1{slash}D17)PG1-Pad15)") (class "Default")
      (node (ref "MCU1") (pin "15") (pinfunction "(DIG1/D17)PG1_15") (pintype "bidirectional"))
    )
    (net (code "54") (name "unconnected-(MCU1-(DIG3{slash}D16)PG0-Pad14)") (class "Default")
      (node (ref "MCU1") (pin "14") (pinfunction "(DIG3/D16)PG0_14") (pintype "bidirectional"))
    )
    (net (code "55") (name "unconnected-(MCU1-(ICP1{slash}D22)PD4-Pad29)") (class "Default")
      (node (ref "MCU1") (pin "29") (pinfunction "(ICP1/D22)PD4_29") (pintype "bidirectional"))
    )
    (net (code "56") (name "unconnected-(MCU1-(ICP3{slash}INT7{slash}CLKO{slash}D7)PE7-Pad53)") (class "Default")
      (node (ref "MCU1") (pin "53") (pinfunction "(ICP3/INT7/CLKO/D7)PE7_53") (pintype "bidirectional"))
    )
    (net (code "57") (name "unconnected-(MCU1-(INT0{slash}SCL{slash}D15)PD0-Pad25)") (class "Default")
      (node (ref "MCU1") (pin "25") (pinfunction "(INT0/SCL/D15)PD0_25") (pintype "bidirectional"))
    )
    (net (code "58") (name "unconnected-(MCU1-(INT1{slash}SDA{slash}D14)PD1-Pad26)") (class "Default")
      (node (ref "MCU1") (pin "26") (pinfunction "(INT1/SDA/D14)PD1_26") (pintype "bidirectional"))
    )
    (net (code "59") (name "unconnected-(MCU1-(INT2{slash}RXD1{slash}D20)PD2-Pad27)") (class "Default")
      (node (ref "MCU1") (pin "27") (pinfunction "(INT2/RXD1/D20)PD2_27") (pintype "bidirectional"))
    )
    (net (code "60") (name "unconnected-(MCU1-(INT3{slash}TXD1{slash}D21)PD3-Pad28)") (class "Default")
      (node (ref "MCU1") (pin "28") (pinfunction "(INT3/TXD1/D21)PD3_28") (pintype "bidirectional"))
    )
    (net (code "61") (name "unconnected-(MCU1-(OC0B{slash}D19-PWM19)PG5-Pad19)") (class "Default")
      (node (ref "MCU1") (pin "19") (pinfunction "(OC0B/D19-PWM19)PG5_19") (pintype "bidirectional"))
    )
    (net (code "62") (name "unconnected-(MCU1-(PCINT0{slash}SSN{slash}D10)PB0-Pad36)") (class "Default")
      (node (ref "MCU1") (pin "36") (pinfunction "(PCINT0/SSN/D10)PB0_36") (pintype "bidirectional"))
    )
    (net (code "63") (name "unconnected-(MCU1-(PCINT6{slash}OC1B{slash}D34-PWM34)PB6-Pad42)") (class "Default")
      (node (ref "MCU1") (pin "42") (pinfunction "(PCINT6/OC1B/D34-PWM34)PB6_42") (pintype "bidirectional"))
    )
    (net (code "64") (name "unconnected-(MCU1-(PCINT7{slash}OC0A{slash}OC1C{slash}D35-PWM35)PB7-Pad43)") (class "Default")
      (node (ref "MCU1") (pin "43") (pinfunction "(PCINT7/OC0A/OC1C/D35-PWM35)PB7_43") (pintype "bidirectional"))
    )
    (net (code "65") (name "unconnected-(MCU1-(T0{slash}D25)PD7-Pad32)") (class "Default")
      (node (ref "MCU1") (pin "32") (pinfunction "(T0/D25)PD7_32") (pintype "bidirectional"))
    )
    (net (code "66") (name "unconnected-(MCU1-(T1{slash}D24)PD6-Pad31)") (class "Default")
      (node (ref "MCU1") (pin "31") (pinfunction "(T1/D24)PD6_31") (pintype "bidirectional"))
    )
    (net (code "67") (name "unconnected-(MCU1-(T3{slash}INT6{slash}D6)PE6-Pad52)") (class "Default")
      (node (ref "MCU1") (pin "52") (pinfunction "(T3/INT6/D6)PE6_52") (pintype "bidirectional"))
    )
    (net (code "68") (name "unconnected-(MCU1-(TOSC1)PG4-Pad18)") (class "Default")
      (node (ref "MCU1") (pin "18") (pinfunction "(TOSC1)PG4_18") (pintype "bidirectional"))
    )
    (net (code "69") (name "unconnected-(MCU1-(TOSC2)PG3-Pad17)") (class "Default")
      (node (ref "MCU1") (pin "17") (pinfunction "(TOSC2)PG3_17") (pintype "bidirectional"))
    )
    (net (code "70") (name "unconnected-(MCU1-(XCK0{slash}AIN0{slash}D2)PE2-Pad48)") (class "Default")
      (node (ref "MCU1") (pin "48") (pinfunction "(XCK0/AIN0/D2)PE2_48") (pintype "bidirectional"))
    )
    (net (code "71") (name "unconnected-(MCU1-(XCK1{slash}D23)PD5-Pad30)") (class "Default")
      (node (ref "MCU1") (pin "30") (pinfunction "(XCK1/D23)PD5_30") (pintype "bidirectional"))
    )
    (net (code "72") (name "unconnected-(MCU1-AREF-Pad62)") (class "Default")
      (node (ref "MCU1") (pin "62") (pinfunction "AREF_62") (pintype "passive"))
    )
    (net (code "73") (name "unconnected-(MCU1-RSTON-Pad13)") (class "Default")
      (node (ref "MCU1") (pin "13") (pinfunction "RSTON_13") (pintype "bidirectional"))
    )
    (net (code "74") (name "unconnected-(SW1-S2-Pad3)") (class "Default")
      (node (ref "SW1") (pin "3") (pinfunction "S2_3") (pintype "passive"))
    )
    (net (code "75") (name "unconnected-(VREG-MCU-FB{slash}NC-Pad7)") (class "Default")
      (node (ref "VREG-MCU") (pin "7") (pinfunction "FB/NC_7") (pintype "bidirectional"))
    )
    (net (code "76") (name "unconnected-(VREG-MCU-PG-Pad8)") (class "Default")
      (node (ref "VREG-MCU") (pin "8") (pinfunction "PG_8") (pintype "no_connect"))
    )
  )
)
